# SafetyChain.net
KiCad netlist of a schematic drawn in EAGLE
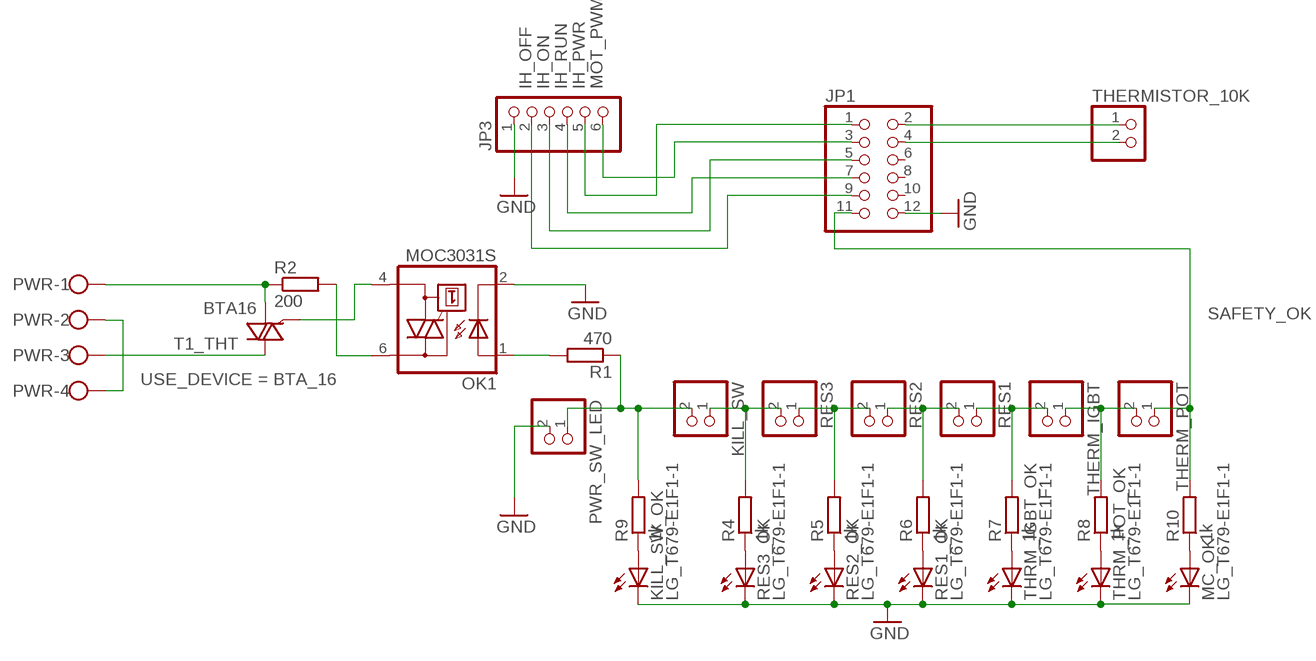
[diagram p0: schematic, sheet 1]

(export (version "E")
  (design (tool "Eeschema 10.0.6"))
  (components
    (comp (ref "JP1")
      (value "PINHD-2X6")
      (footprint "eagle-import:2X06")
      (libsource (lib "eagle-import") (part "PINHD-2X6"))
    )
    (comp (ref "JP3")
      (value "PINHD-1X6")
      (footprint "eagle-import:1X06")
      (libsource (lib "eagle-import") (part "PINHD-1X6"))
    )
    (comp (ref "KILL_SW")
      (value "PINHD-1X2")
      (footprint "eagle-import:1X02")
      (libsource (lib "eagle-import") (part "PINHD-1X2"))
    )
    (comp (ref "KILL_SW_OK")
      (value "LG_T679-E1F1-1")
      (footprint "eagle-import:PLCC2")
      (libsource (lib "eagle-import") (part "_T679-?-1E1F1LG"))
    )
    (comp (ref "MC_OK")
      (value "LG_T679-E1F1-1")
      (footprint "eagle-import:PLCC2")
      (libsource (lib "eagle-import") (part "_T679-?-1E1F1LG"))
    )
    (comp (ref "OK1")
      (value "MOC3031S")
      (footprint "eagle-import:DIL6-SMD")
      (fields (field (name "MF") "FAIRCHILD SEMICONDUCTOR") (field (name "MPN") "MOC3031SM"))
      (libsource (lib "eagle-import") (part "MOC30S31"))
    )
    (comp (ref "PWR")
      (value "W237-4")
      (footprint "eagle-import:W237-4")
      (libsource (lib "eagle-import") (part "W237-4"))
    )
    (comp (ref "PWR_SW_LED")
      (value "PINHD-1X2")
      (footprint "eagle-import:1X02")
      (libsource (lib "eagle-import") (part "PINHD-1X2"))
    )
    (comp (ref "R1")
      (value "470")
      (footprint "eagle-import:M0805")
      (libsource (lib "eagle-import") (part "R-EU_M0805"))
    )
    (comp (ref "R2")
      (value "200")
      (footprint "eagle-import:M0805")
      (libsource (lib "eagle-import") (part "R-EU_M0805"))
    )
    (comp (ref "R4")
      (value "1k")
      (footprint "eagle-import:M0805")
      (libsource (lib "eagle-import") (part "R-EU_M0805"))
    )
    (comp (ref "R5")
      (value "1k")
      (footprint "eagle-import:M0805")
      (libsource (lib "eagle-import") (part "R-EU_M0805"))
    )
    (comp (ref "R6")
      (value "1k")
      (footprint "eagle-import:M0805")
      (libsource (lib "eagle-import") (part "R-EU_M0805"))
    )
    (comp (ref "R7")
      (value "1k")
      (footprint "eagle-import:M0805")
      (libsource (lib "eagle-import") (part "R-EU_M0805"))
    )
    (comp (ref "R8")
      (value "1k")
      (footprint "eagle-import:M0805")
      (libsource (lib "eagle-import") (part "R-EU_M0805"))
    )
    (comp (ref "R9")
      (value "1k")
      (footprint "eagle-import:M0805")
      (libsource (lib "eagle-import") (part "R-EU_M0805"))
    )
    (comp (ref "R10")
      (value "1k")
      (footprint "eagle-import:M0805")
      (libsource (lib "eagle-import") (part "R-EU_M0805"))
    )
    (comp (ref "RES1")
      (value "PINHD-1X2")
      (footprint "eagle-import:1X02")
      (libsource (lib "eagle-import") (part "PINHD-1X2"))
    )
    (comp (ref "RES1_OK")
      (value "LG_T679-E1F1-1")
      (footprint "eagle-import:PLCC2")
      (libsource (lib "eagle-import") (part "_T679-?-1E1F1LG"))
    )
    (comp (ref "RES2")
      (value "PINHD-1X2")
      (footprint "eagle-import:1X02")
      (libsource (lib "eagle-import") (part "PINHD-1X2"))
    )
    (comp (ref "RES2_OK")
      (value "LG_T679-E1F1-1")
      (footprint "eagle-import:PLCC2")
      (libsource (lib "eagle-import") (part "_T679-?-1E1F1LG"))
    )
    (comp (ref "RES3")
      (value "PINHD-1X2")
      (footprint "eagle-import:1X02")
      (libsource (lib "eagle-import") (part "PINHD-1X2"))
    )
    (comp (ref "RES3_OK")
      (value "LG_T679-E1F1-1")
      (footprint "eagle-import:PLCC2")
      (libsource (lib "eagle-import") (part "_T679-?-1E1F1LG"))
    )
    (comp (ref "T1_THT")
      (value "BTA16")
      (footprint "eagle-import:TO220BV")
      (fields (field (name "USE_DEVICE") "BTA_16"))
      (libsource (lib "eagle-import") (part "BT138-V"))
    )
    (comp (ref "THERMISTOR_10K")
      (value "PINHD-1X2")
      (footprint "eagle-import:1X02")
      (libsource (lib "eagle-import") (part "PINHD-1X2"))
    )
    (comp (ref "THERM_IGBT")
      (value "PINHD-1X2")
      (footprint "eagle-import:1X02")
      (libsource (lib "eagle-import") (part "PINHD-1X2"))
    )
    (comp (ref "THERM_POT")
      (value "PINHD-1X2")
      (footprint "eagle-import:1X02")
      (libsource (lib "eagle-import") (part "PINHD-1X2"))
    )
    (comp (ref "THRM_IGBT_OK")
      (value "LG_T679-E1F1-1")
      (footprint "eagle-import:PLCC2")
      (libsource (lib "eagle-import") (part "_T679-?-1E1F1LG"))
    )
    (comp (ref "THRM_POT_OK")
      (value "LG_T679-E1F1-1")
      (footprint "eagle-import:PLCC2")
      (libsource (lib "eagle-import") (part "_T679-?-1E1F1LG"))
    )
  )
  (nets
    (net (code "1") (name "/IH_OFF") (class "Default")
      (node (ref "JP1") (pin "9") (pinfunction "9_9") (pintype "passive"))
      (node (ref "JP3") (pin "2") (pinfunction "2_2") (pintype "passive"))
    )
    (net (code "2") (name "/IH_ON") (class "Default")
      (node (ref "JP1") (pin "5") (pinfunction "5_5") (pintype "passive"))
      (node (ref "JP3") (pin "3") (pinfunction "3_3") (pintype "passive"))
    )
    (net (code "3") (name "/IH_PWR") (class "Default")
      (node (ref "JP1") (pin "1") (pinfunction "1_1") (pintype "passive"))
      (node (ref "JP3") (pin "5") (pinfunction "5_5") (pintype "passive"))
    )
    (net (code "4") (name "/IH_RUN") (class "Default")
      (node (ref "JP1") (pin "7") (pinfunction "7_7") (pintype "passive"))
      (node (ref "JP3") (pin "4") (pinfunction "4_4") (pintype "passive"))
    )
    (net (code "5") (name "/MOT_PWM") (class "Default")
      (node (ref "JP1") (pin "3") (pinfunction "3_3") (pintype "passive"))
      (node (ref "JP3") (pin "6") (pinfunction "6_6") (pintype "passive"))
    )
    (net (code "6") (name "/SAFETY_OK") (class "Default")
      (node (ref "JP1") (pin "11") (pinfunction "11_11") (pintype "passive"))
      (node (ref "R10") (pin "2") (pinfunction "2_2") (pintype "passive"))
      (node (ref "THERM_POT") (pin "1") (pinfunction "1_1") (pintype "passive"))
    )
    (net (code "7") (name "GND") (class "Default")
      (node (ref "JP1") (pin "12") (pinfunction "12_12") (pintype "passive"))
      (node (ref "JP3") (pin "1") (pinfunction "1_1") (pintype "passive"))
      (node (ref "KILL_SW_OK") (pin "C") (pinfunction "C_C") (pintype "passive"))
      (node (ref "MC_OK") (pin "C") (pinfunction "C_C") (pintype "passive"))
      (node (ref "OK1") (pin "2") (pinfunction "C_2") (pintype "passive"))
      (node (ref "PWR_SW_LED") (pin "2") (pinfunction "2_2") (pintype "passive"))
      (node (ref "RES1_OK") (pin "C") (pinfunction "C_C") (pintype "passive"))
      (node (ref "RES2_OK") (pin "C") (pinfunction "C_C") (pintype "passive"))
      (node (ref "RES3_OK") (pin "C") (pinfunction "C_C") (pintype "passive"))
      (node (ref "THRM_IGBT_OK") (pin "C") (pinfunction "C_C") (pintype "passive"))
      (node (ref "THRM_POT_OK") (pin "C") (pinfunction "C_C") (pintype "passive"))
    )
    (net (code "8") (name "Net-(JP1-Pad2)") (class "Default")
      (node (ref "JP1") (pin "2") (pinfunction "2_2") (pintype "passive"))
      (node (ref "THERMISTOR_10K") (pin "1") (pinfunction "1_1") (pintype "passive"))
    )
    (net (code "9") (name "Net-(JP1-Pad4)") (class "Default")
      (node (ref "JP1") (pin "4") (pinfunction "4_4") (pintype "passive"))
      (node (ref "THERMISTOR_10K") (pin "2") (pinfunction "2_2") (pintype "passive"))
    )
    (net (code "10") (name "Net-(KILL_SW-Pad1)") (class "Default")
      (node (ref "KILL_SW") (pin "1") (pinfunction "1_1") (pintype "passive"))
      (node (ref "R4") (pin "2") (pinfunction "2_2") (pintype "passive"))
      (node (ref "RES3") (pin "2") (pinfunction "2_2") (pintype "passive"))
    )
    (net (code "11") (name "Net-(KILL_SW-Pad2)") (class "Default")
      (node (ref "KILL_SW") (pin "2") (pinfunction "2_2") (pintype "passive"))
      (node (ref "PWR_SW_LED") (pin "1") (pinfunction "1_1") (pintype "passive"))
      (node (ref "R1") (pin "1") (pinfunction "1_1") (pintype "passive"))
      (node (ref "R9") (pin "2") (pinfunction "2_2") (pintype "passive"))
    )
    (net (code "12") (name "Net-(KILL_SW_OK-PadA)") (class "Default")
      (node (ref "KILL_SW_OK") (pin "A") (pinfunction "A_A") (pintype "passive"))
      (node (ref "R9") (pin "1") (pinfunction "1_1") (pintype "passive"))
    )
    (net (code "13") (name "Net-(MC_OK-PadA)") (class "Default")
      (node (ref "MC_OK") (pin "A") (pinfunction "A_A") (pintype "passive"))
      (node (ref "R10") (pin "1") (pinfunction "1_1") (pintype "passive"))
    )
    (net (code "14") (name "Net-(OK1-A)") (class "Default")
      (node (ref "OK1") (pin "1") (pinfunction "A_1") (pintype "passive"))
      (node (ref "R1") (pin "2") (pinfunction "2_2") (pintype "passive"))
    )
    (net (code "15") (name "Net-(OK1-A1)") (class "Default")
      (node (ref "OK1") (pin "4") (pinfunction "A1_4") (pintype "passive"))
      (node (ref "T1_THT") (pin "G") (pinfunction "G_G") (pintype "passive"))
    )
    (net (code "16") (name "Net-(OK1-A2)") (class "Default")
      (node (ref "OK1") (pin "6") (pinfunction "A2_6") (pintype "passive"))
      (node (ref "R2") (pin "2") (pinfunction "2_2") (pintype "passive"))
    )
    (net (code "17") (name "Net-(PWRA-KL)") (class "Default")
      (node (ref "PWR") (pin "1") (pinfunction "KL_1") (pintype "passive"))
      (node (ref "R2") (pin "1") (pinfunction "1_1") (pintype "passive"))
      (node (ref "T1_THT") (pin "T1") (pinfunction "A1_T1") (pintype "passive"))
    )
    (net (code "18") (name "Net-(PWRB-KL)") (class "Default")
      (node (ref "PWR") (pin "2") (pinfunction "KL_2") (pintype "passive"))
      (node (ref "PWR") (pin "4") (pinfunction "KL_4") (pintype "passive"))
    )
    (net (code "19") (name "Net-(PWRC-KL)") (class "Default")
      (node (ref "PWR") (pin "3") (pinfunction "KL_3") (pintype "passive"))
      (node (ref "T1_THT") (pin "T2") (pinfunction "A2_T2") (pintype "passive"))
    )
    (net (code "20") (name "Net-(R4-Pad1)") (class "Default")
      (node (ref "R4") (pin "1") (pinfunction "1_1") (pintype "passive"))
      (node (ref "RES3_OK") (pin "A") (pinfunction "A_A") (pintype "passive"))
    )
    (net (code "21") (name "Net-(R5-Pad1)") (class "Default")
      (node (ref "R5") (pin "1") (pinfunction "1_1") (pintype "passive"))
      (node (ref "RES2_OK") (pin "A") (pinfunction "A_A") (pintype "passive"))
    )
    (net (code "22") (name "Net-(R5-Pad2)") (class "Default")
      (node (ref "R5") (pin "2") (pinfunction "2_2") (pintype "passive"))
      (node (ref "RES2") (pin "2") (pinfunction "2_2") (pintype "passive"))
      (node (ref "RES3") (pin "1") (pinfunction "1_1") (pintype "passive"))
    )
    (net (code "23") (name "Net-(R6-Pad1)") (class "Default")
      (node (ref "R6") (pin "1") (pinfunction "1_1") (pintype "passive"))
      (node (ref "RES1_OK") (pin "A") (pinfunction "A_A") (pintype "passive"))
    )
    (net (code "24") (name "Net-(R6-Pad2)") (class "Default")
      (node (ref "R6") (pin "2") (pinfunction "2_2") (pintype "passive"))
      (node (ref "RES1") (pin "2") (pinfunction "2_2") (pintype "passive"))
      (node (ref "RES2") (pin "1") (pinfunction "1_1") (pintype "passive"))
    )
    (net (code "25") (name "Net-(R7-Pad1)") (class "Default")
      (node (ref "R7") (pin "1") (pinfunction "1_1") (pintype "passive"))
      (node (ref "THRM_IGBT_OK") (pin "A") (pinfunction "A_A") (pintype "passive"))
    )
    (net (code "26") (name "Net-(R7-Pad2)") (class "Default")
      (node (ref "R7") (pin "2") (pinfunction "2_2") (pintype "passive"))
      (node (ref "RES1") (pin "1") (pinfunction "1_1") (pintype "passive"))
      (node (ref "THERM_IGBT") (pin "2") (pinfunction "2_2") (pintype "passive"))
    )
    (net (code "27") (name "Net-(R8-Pad1)") (class "Default")
      (node (ref "R8") (pin "1") (pinfunction "1_1") (pintype "passive"))
      (node (ref "THRM_POT_OK") (pin "A") (pinfunction "A_A") (pintype "passive"))
    )
    (net (code "28") (name "Net-(R8-Pad2)") (class "Default")
      (node (ref "R8") (pin "2") (pinfunction "2_2") (pintype "passive"))
      (node (ref "THERM_IGBT") (pin "1") (pinfunction "1_1") (pintype "passive"))
      (node (ref "THERM_POT") (pin "2") (pinfunction "2_2") (pintype "passive"))
    )
    (net (code "29") (name "unconnected-(JP1-Pad6)") (class "Default")
      (node (ref "JP1") (pin "6") (pinfunction "6_6") (pintype "passive"))
    )
    (net (code "30") (name "unconnected-(JP1-Pad8)") (class "Default")
      (node (ref "JP1") (pin "8") (pinfunction "8_8") (pintype "passive"))
    )
    (net (code "31") (name "unconnected-(JP1-Pad10)") (class "Default")
      (node (ref "JP1") (pin "10") (pinfunction "10_10") (pintype "passive"))
    )
  )
)
